# pv_emulator.net
KiCad netlist of a schematic drawn in EAGLE
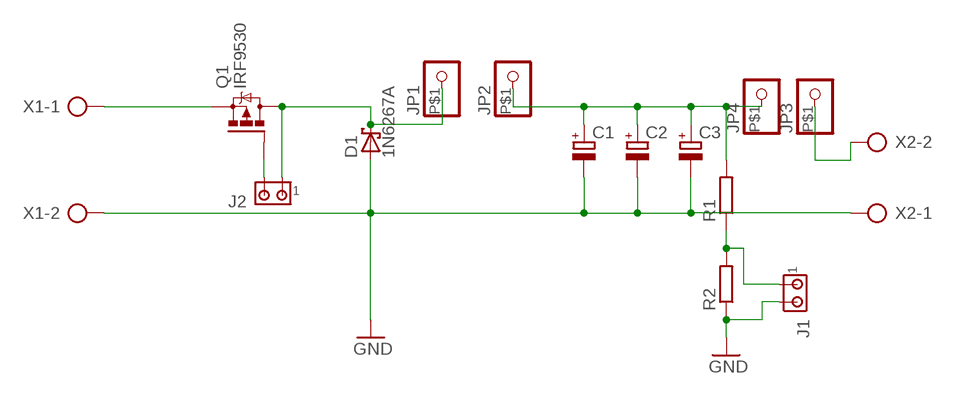
[diagram p0: schematic, sheet 1]

(export (version "E")
  (design (tool "Eeschema 10.0.6"))
  (components
    (comp (ref "C1")
      (value "CPOL-EUE5-10.5")
      (footprint "eagle-import:E5-10,5")
      (libsource (lib "eagle-import") (part "CPOL-EUE5-10.5"))
    )
    (comp (ref "C2")
      (value "CPOL-EUE5-10.5")
      (footprint "eagle-import:E5-10,5")
      (libsource (lib "eagle-import") (part "CPOL-EUE5-10.5"))
    )
    (comp (ref "C3")
      (value "CPOL-EUE5-10.5")
      (footprint "eagle-import:E5-10,5")
      (libsource (lib "eagle-import") (part "CPOL-EUE5-10.5"))
    )
    (comp (ref "D1")
      (value "1N6267A")
      (footprint "eagle-import:C4111-15")
      (libsource (lib "eagle-import") (part "1N6267A"))
    )
    (comp (ref "J1")
      (value "MTA02-100")
      (footprint "eagle-import:10X02MTA")
      (libsource (lib "eagle-import") (part "MTA02-100"))
    )
    (comp (ref "J2")
      (value "MTA02-100")
      (footprint "eagle-import:10X02MTA")
      (libsource (lib "eagle-import") (part "MTA02-100"))
    )
    (comp (ref "JP1")
      (value "PINHD-1X1-BIGPOGO")
      (footprint "eagle-import:1X1-BIGPOGO")
      (libsource (lib "eagle-import") (part "PINHD-1X1-BIGPOGO"))
    )
    (comp (ref "JP2")
      (value "PINHD-1X1-BIGPOGO")
      (footprint "eagle-import:1X1-BIGPOGO")
      (libsource (lib "eagle-import") (part "PINHD-1X1-BIGPOGO"))
    )
    (comp (ref "JP3")
      (value "PINHD-1X1-BIGPOGO")
      (footprint "eagle-import:1X1-BIGPOGO")
      (libsource (lib "eagle-import") (part "PINHD-1X1-BIGPOGO"))
    )
    (comp (ref "JP4")
      (value "PINHD-1X1-BIGPOGO")
      (footprint "eagle-import:1X1-BIGPOGO")
      (libsource (lib "eagle-import") (part "PINHD-1X1-BIGPOGO"))
    )
    (comp (ref "Q1")
      (value "IRF9530")
      (footprint "eagle-import:TO220BV")
      (libsource (lib "eagle-import") (part "IRF9530"))
    )
    (comp (ref "R1")
      (value "R-EU_0204/7")
      (footprint "eagle-import:0204_7")
      (libsource (lib "eagle-import") (part "R-EU_0204/7"))
    )
    (comp (ref "R2")
      (value "R-EU_0204/7")
      (footprint "eagle-import:0204_7")
      (libsource (lib "eagle-import") (part "R-EU_0204/7"))
    )
    (comp (ref "X1")
      (value "AK300/2")
      (footprint "eagle-import:AK300_2")
      (libsource (lib "eagle-import") (part "AK300/2"))
    )
    (comp (ref "X2")
      (value "AK300/2")
      (footprint "eagle-import:AK300_2")
      (libsource (lib "eagle-import") (part "AK300/2"))
    )
  )
  (nets
    (net (code "1") (name "GND") (class "Default")
      (node (ref "C1") (pin "-") (pinfunction "-_-") (pintype "passive"))
      (node (ref "C2") (pin "-") (pinfunction "-_-") (pintype "passive"))
      (node (ref "C3") (pin "-") (pinfunction "-_-") (pintype "passive"))
      (node (ref "D1") (pin "A") (pinfunction "A_A") (pintype "passive"))
      (node (ref "J1") (pin "2") (pinfunction "2_2") (pintype "passive"))
      (node (ref "R2") (pin "1") (pinfunction "1_1") (pintype "passive"))
      (node (ref "X1") (pin "2") (pinfunction "KL_2") (pintype "passive"))
      (node (ref "X2") (pin "1") (pinfunction "KL_1") (pintype "passive"))
    )
    (net (code "2") (name "Net-(J1-Pad1)") (class "Default")
      (node (ref "J1") (pin "1") (pinfunction "1_1") (pintype "passive"))
      (node (ref "R1") (pin "1") (pinfunction "1_1") (pintype "passive"))
      (node (ref "R2") (pin "2") (pinfunction "2_2") (pintype "passive"))
    )
    (net (code "3") (name "Net-(J2-Pad2)") (class "Default")
      (node (ref "J2") (pin "2") (pinfunction "2_2") (pintype "passive"))
      (node (ref "Q1") (pin "G") (pinfunction "G_G") (pintype "passive"))
    )
    (net (code "4") (name "Net-(JP1-1)") (class "Default")
      (node (ref "D1") (pin "C") (pinfunction "C_C") (pintype "passive"))
      (node (ref "J2") (pin "1") (pinfunction "1_1") (pintype "passive"))
      (node (ref "JP1") (pin "P$1") (pinfunction "1_P$1") (pintype "passive"))
      (node (ref "Q1") (pin "D") (pinfunction "D_D") (pintype "passive"))
    )
    (net (code "5") (name "Net-(JP2-1)") (class "Default")
      (node (ref "C1") (pin "+") (pinfunction "+_+") (pintype "passive"))
      (node (ref "C2") (pin "+") (pinfunction "+_+") (pintype "passive"))
      (node (ref "C3") (pin "+") (pinfunction "+_+") (pintype "passive"))
      (node (ref "JP2") (pin "P$1") (pinfunction "1_P$1") (pintype "passive"))
      (node (ref "JP4") (pin "P$1") (pinfunction "1_P$1") (pintype "passive"))
      (node (ref "R1") (pin "2") (pinfunction "2_2") (pintype "passive"))
    )
    (net (code "6") (name "Net-(JP3-1)") (class "Default")
      (node (ref "JP3") (pin "P$1") (pinfunction "1_P$1") (pintype "passive"))
      (node (ref "X2") (pin "2") (pinfunction "KL_2") (pintype "passive"))
    )
    (net (code "7") (name "Net-(X1A-KL)") (class "Default")
      (node (ref "Q1") (pin "S") (pinfunction "S_S") (pintype "passive"))
      (node (ref "X1") (pin "1") (pinfunction "KL_1") (pintype "passive"))
    )
  )
)
